# BBBL-CAN-GPS-RC-Interface.net
KiCad netlist of a schematic drawn in EAGLE
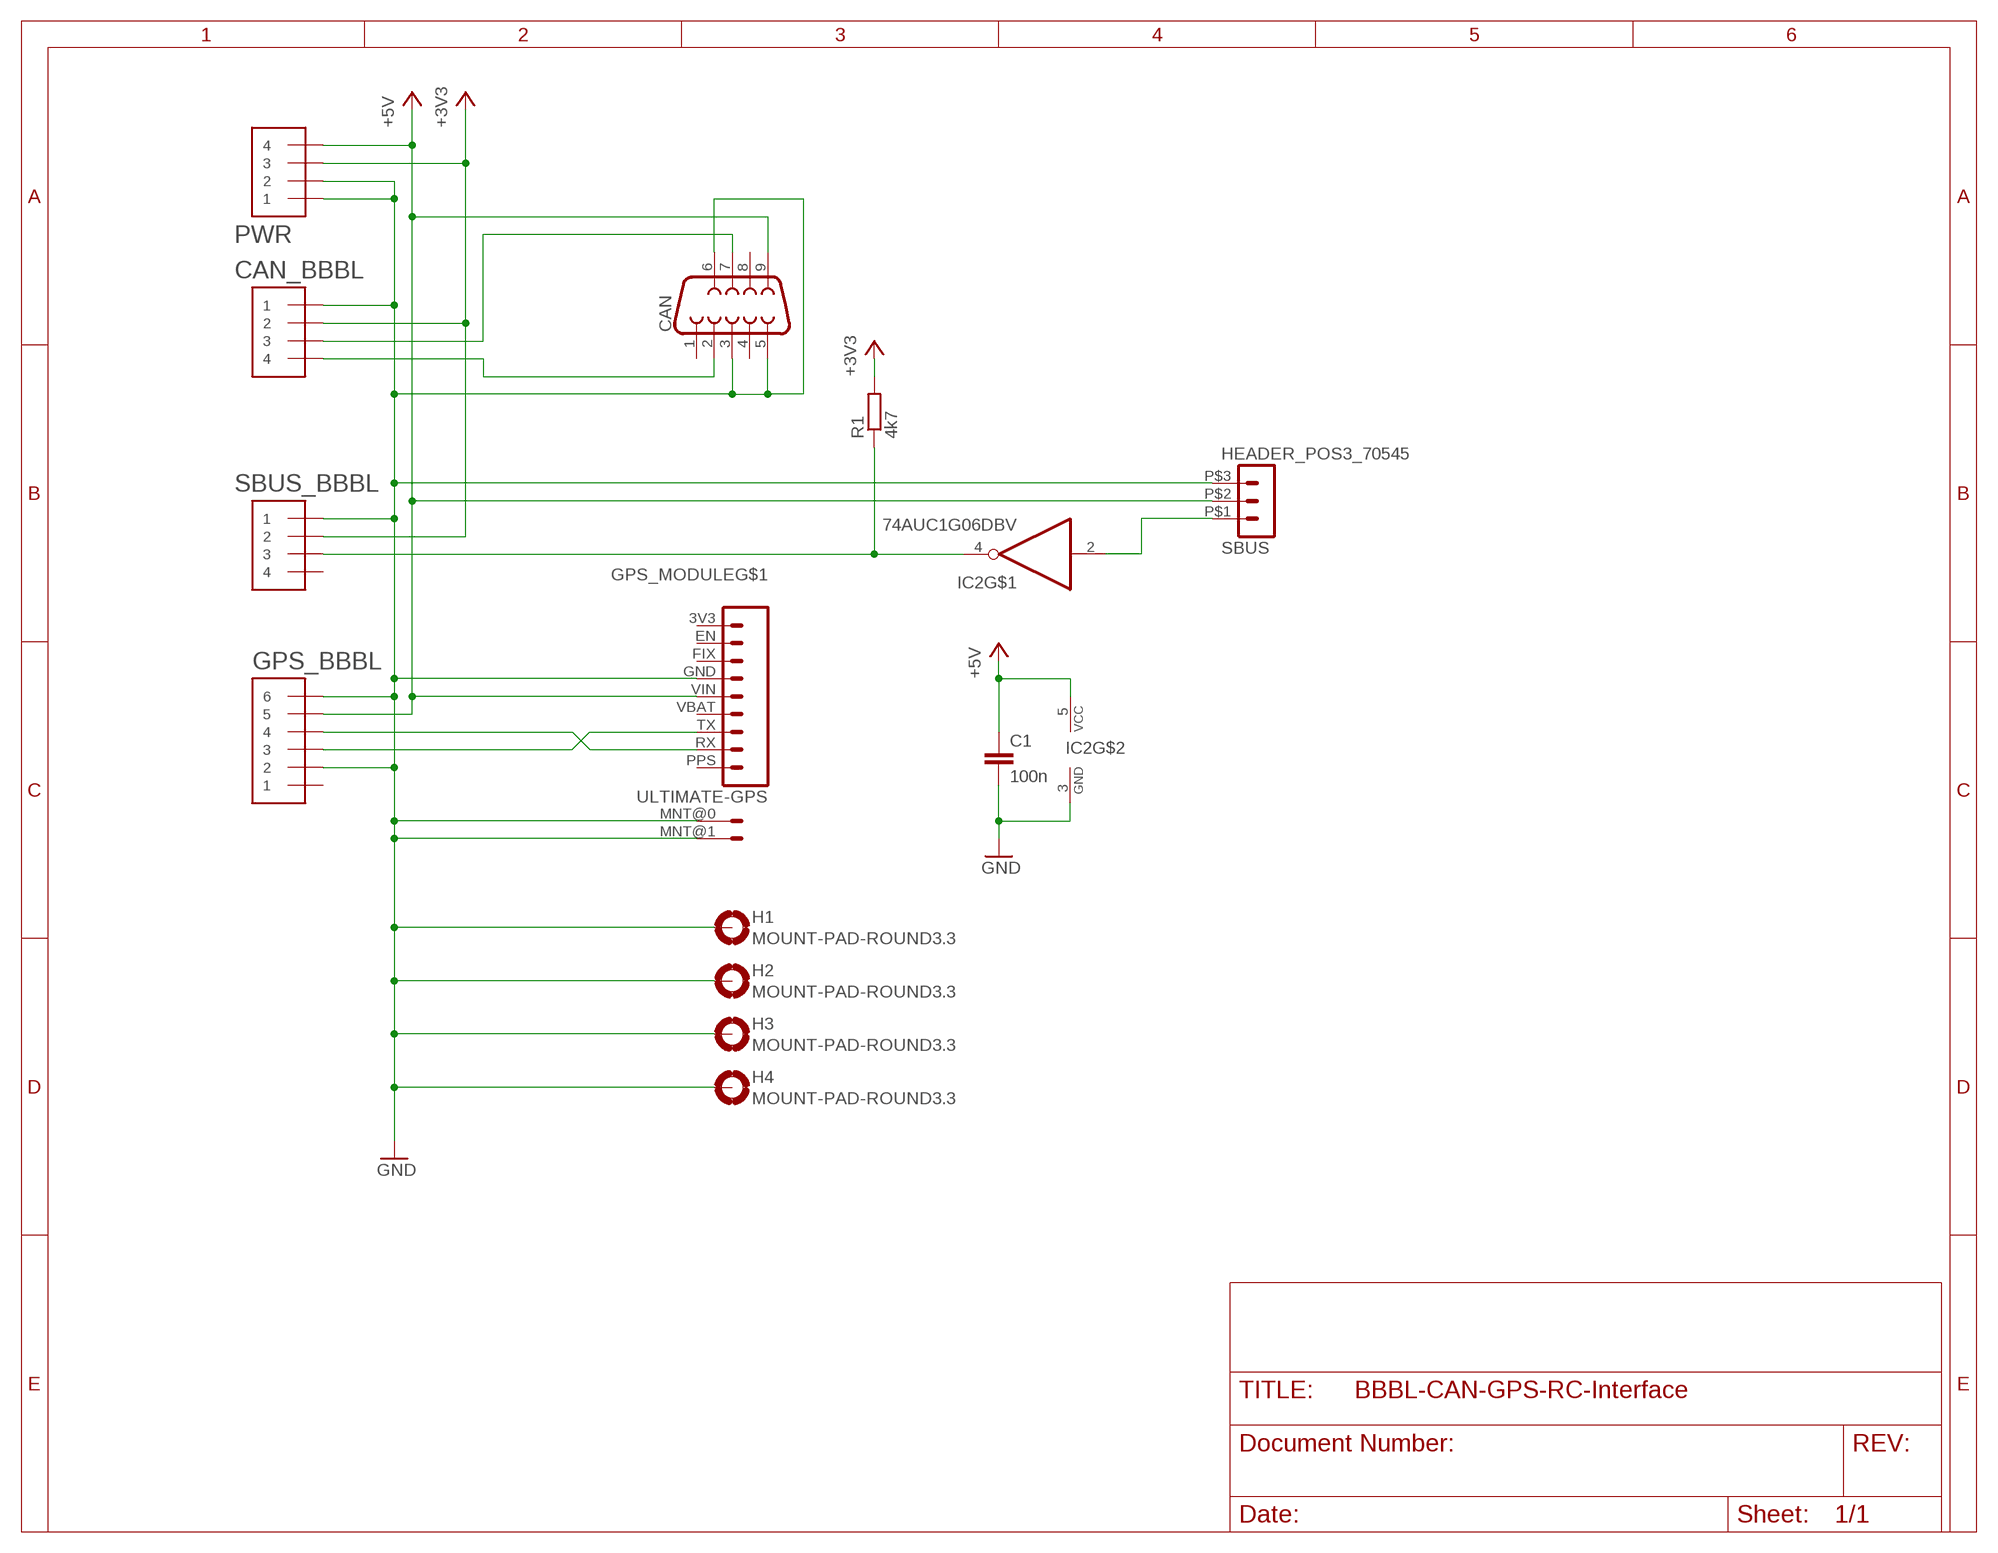
[diagram p0: schematic, sheet 1]

(export (version "E")
  (design (tool "Eeschema 10.0.6"))
  (components
    (comp (ref "C1")
      (value "100n")
      (footprint "eagle-import:C0603")
      (libsource (lib "eagle-import") (part "C-EUC0603"))
    )
    (comp (ref "CAN")
      (value "DB9MALE")
      (footprint "eagle-import:DB9_MALE")
      (libsource (lib "eagle-import") (part "DB9MALE"))
    )
    (comp (ref "CAN_BBBL")
      (value "STRAWSON_EAGLE_LIB_JST_SH_4")
      (footprint "eagle-import:STRAWSON_EAGLE_LIB_JST_SH_4_SMD")
      (libsource (lib "eagle-import") (part "STRAWSON_EAGLE_LIB_JST_SH_4"))
    )
    (comp (ref "GPS_BBBL")
      (value "STRAWSON_EAGLE_LIB_JST_SH_6")
      (footprint "eagle-import:STRAWSON_EAGLE_LIB_JST_SH_6")
      (libsource (lib "eagle-import") (part "STRAWSON_EAGLE_LIB_JST_SH_6"))
    )
    (comp (ref "GPS_MODULE")
      (value "ULTIMATE-GPS")
      (footprint "eagle-import:ULTIMATE-GPS")
      (libsource (lib "eagle-import") (part "ULTIMATE-GPS"))
    )
    (comp (ref "H1")
      (value "MOUNT-PAD-ROUND3.3")
      (footprint "eagle-import:3,3-PAD")
      (libsource (lib "eagle-import") (part "MOUNT-PAD-ROUND3.3"))
    )
    (comp (ref "H2")
      (value "MOUNT-PAD-ROUND3.3")
      (footprint "eagle-import:3,3-PAD")
      (libsource (lib "eagle-import") (part "MOUNT-PAD-ROUND3.3"))
    )
    (comp (ref "H3")
      (value "MOUNT-PAD-ROUND3.3")
      (footprint "eagle-import:3,3-PAD")
      (libsource (lib "eagle-import") (part "MOUNT-PAD-ROUND3.3"))
    )
    (comp (ref "H4")
      (value "MOUNT-PAD-ROUND3.3")
      (footprint "eagle-import:3,3-PAD")
      (libsource (lib "eagle-import") (part "MOUNT-PAD-ROUND3.3"))
    )
    (comp (ref "IC2")
      (value "74AUC1G06DBV")
      (footprint "eagle-import:SOT23-5")
      (libsource (lib "eagle-import") (part "741G06DBVAUC"))
    )
    (comp (ref "PWR")
      (value "STRAWSON_EAGLE_LIB_JST_SH_4")
      (footprint "eagle-import:STRAWSON_EAGLE_LIB_JST_SH_4_SMD")
      (libsource (lib "eagle-import") (part "STRAWSON_EAGLE_LIB_JST_SH_4"))
    )
    (comp (ref "R1")
      (value "4k7")
      (footprint "eagle-import:R0603")
      (libsource (lib "eagle-import") (part "R-EU_R0603"))
    )
    (comp (ref "SBUS")
      (value "HEADER_POS3_70545")
      (footprint "eagle-import:70545-POS3")
      (libsource (lib "eagle-import") (part "HEADER_POS3_?70545"))
    )
    (comp (ref "SBUS_BBBL")
      (value "STRAWSON_EAGLE_LIB_JST_SH_4")
      (footprint "eagle-import:STRAWSON_EAGLE_LIB_JST_SH_4_SMD")
      (libsource (lib "eagle-import") (part "STRAWSON_EAGLE_LIB_JST_SH_4"))
    )
  )
  (nets
    (net (code "1") (name "+3V3") (class "Default")
      (node (ref "CAN_BBBL") (pin "2") (pinfunction "2_2") (pintype "bidirectional"))
      (node (ref "PWR") (pin "3") (pinfunction "3_3") (pintype "bidirectional"))
      (node (ref "R1") (pin "2") (pinfunction "2_2") (pintype "passive"))
      (node (ref "SBUS_BBBL") (pin "2") (pinfunction "2_2") (pintype "bidirectional"))
    )
    (net (code "2") (name "+5V") (class "Default")
      (node (ref "C1") (pin "1") (pinfunction "1_1") (pintype "passive"))
      (node (ref "CAN") (pin "9") (pinfunction "9_9") (pintype "passive"))
      (node (ref "GPS_BBBL") (pin "5") (pinfunction "5_5") (pintype "bidirectional"))
      (node (ref "GPS_MODULE") (pin "VIN") (pinfunction "5_VIN") (pintype "passive"))
      (node (ref "IC2") (pin "5") (pinfunction "VCC_5") (pintype "power_in"))
      (node (ref "PWR") (pin "4") (pinfunction "4_4") (pintype "bidirectional"))
      (node (ref "SBUS") (pin "P$2") (pinfunction "2_P$2") (pintype "passive"))
    )
    (net (code "3") (name "GND") (class "Default")
      (node (ref "C1") (pin "2") (pinfunction "2_2") (pintype "passive"))
      (node (ref "CAN") (pin "3") (pinfunction "3_3") (pintype "passive"))
      (node (ref "CAN") (pin "5") (pinfunction "5_5") (pintype "passive"))
      (node (ref "CAN") (pin "6") (pinfunction "6_6") (pintype "passive"))
      (node (ref "CAN_BBBL") (pin "1") (pinfunction "1_1") (pintype "bidirectional"))
      (node (ref "GPS_BBBL") (pin "2") (pinfunction "2_2") (pintype "bidirectional"))
      (node (ref "GPS_BBBL") (pin "6") (pinfunction "6_6") (pintype "bidirectional"))
      (node (ref "GPS_MODULE") (pin "GND") (pinfunction "6_GND") (pintype "passive"))
      (node (ref "GPS_MODULE") (pin "MNT@0") (pinfunction "9_MNT@0") (pintype "passive"))
      (node (ref "GPS_MODULE") (pin "MNT@1") (pinfunction "9_MNT@1") (pintype "passive"))
      (node (ref "H1") (pin "B3,3") (pinfunction "MOUNT_B3,3") (pintype "passive"))
      (node (ref "H2") (pin "B3,3") (pinfunction "MOUNT_B3,3") (pintype "passive"))
      (node (ref "H3") (pin "B3,3") (pinfunction "MOUNT_B3,3") (pintype "passive"))
      (node (ref "H4") (pin "B3,3") (pinfunction "MOUNT_B3,3") (pintype "passive"))
      (node (ref "IC2") (pin "3") (pinfunction "GND_3") (pintype "power_in"))
      (node (ref "PWR") (pin "1") (pinfunction "1_1") (pintype "bidirectional"))
      (node (ref "PWR") (pin "2") (pinfunction "2_2") (pintype "bidirectional"))
      (node (ref "SBUS") (pin "P$3") (pinfunction "3_P$3") (pintype "passive"))
      (node (ref "SBUS_BBBL") (pin "1") (pinfunction "1_1") (pintype "bidirectional"))
    )
    (net (code "4") (name "Net-(CAN-Pad2)") (class "Default")
      (node (ref "CAN") (pin "2") (pinfunction "2_2") (pintype "passive"))
      (node (ref "CAN_BBBL") (pin "4") (pinfunction "4_4") (pintype "bidirectional"))
    )
    (net (code "5") (name "Net-(CAN-Pad7)") (class "Default")
      (node (ref "CAN") (pin "7") (pinfunction "7_7") (pintype "passive"))
      (node (ref "CAN_BBBL") (pin "3") (pinfunction "3_3") (pintype "bidirectional"))
    )
    (net (code "6") (name "Net-(GPS_MODULEA-2)") (class "Default")
      (node (ref "GPS_BBBL") (pin "4") (pinfunction "4_4") (pintype "bidirectional"))
      (node (ref "GPS_MODULE") (pin "RX") (pinfunction "2_RX") (pintype "passive"))
    )
    (net (code "7") (name "Net-(GPS_MODULEA-3)") (class "Default")
      (node (ref "GPS_BBBL") (pin "3") (pinfunction "3_3") (pintype "bidirectional"))
      (node (ref "GPS_MODULE") (pin "TX") (pinfunction "3_TX") (pintype "passive"))
    )
    (net (code "8") (name "Net-(IC2A-I)") (class "Default")
      (node (ref "IC2") (pin "2") (pinfunction "I_2") (pintype "input"))
      (node (ref "SBUS") (pin "P$1") (pinfunction "1_P$1") (pintype "passive"))
    )
    (net (code "9") (name "Net-(IC2A-O)") (class "Default")
      (node (ref "IC2") (pin "4") (pinfunction "O_4") (pintype "open_collector"))
      (node (ref "R1") (pin "1") (pinfunction "1_1") (pintype "passive"))
      (node (ref "SBUS_BBBL") (pin "3") (pinfunction "3_3") (pintype "bidirectional"))
    )
    (net (code "10") (name "unconnected-(CAN-Pad1)") (class "Default")
      (node (ref "CAN") (pin "1") (pinfunction "1_1") (pintype "passive"))
    )
    (net (code "11") (name "unconnected-(CAN-Pad4)") (class "Default")
      (node (ref "CAN") (pin "4") (pinfunction "4_4") (pintype "passive"))
    )
    (net (code "12") (name "unconnected-(CAN-Pad8)") (class "Default")
      (node (ref "CAN") (pin "8") (pinfunction "8_8") (pintype "passive"))
    )
    (net (code "13") (name "unconnected-(GPS_BBBL-Pad1)") (class "Default")
      (node (ref "GPS_BBBL") (pin "1") (pinfunction "1_1") (pintype "bidirectional"))
    )
    (net (code "14") (name "unconnected-(GPS_MODULEA-1-PadPPS)") (class "Default")
      (node (ref "GPS_MODULE") (pin "PPS") (pinfunction "1_PPS") (pintype "passive"))
    )
    (net (code "15") (name "unconnected-(GPS_MODULEA-4-PadVBAT)") (class "Default")
      (node (ref "GPS_MODULE") (pin "VBAT") (pinfunction "4_VBAT") (pintype "passive"))
    )
    (net (code "16") (name "unconnected-(GPS_MODULEA-7-PadFIX)") (class "Default")
      (node (ref "GPS_MODULE") (pin "FIX") (pinfunction "7_FIX") (pintype "passive"))
    )
    (net (code "17") (name "unconnected-(GPS_MODULEA-8-PadEN)") (class "Default")
      (node (ref "GPS_MODULE") (pin "EN") (pinfunction "8_EN") (pintype "passive"))
    )
    (net (code "18") (name "unconnected-(GPS_MODULEA-9-Pad3V3)") (class "Default")
      (node (ref "GPS_MODULE") (pin "3V3") (pinfunction "9_3V3") (pintype "passive"))
    )
    (net (code "19") (name "unconnected-(SBUS_BBBL-Pad4)") (class "Default")
      (node (ref "SBUS_BBBL") (pin "4") (pinfunction "4_4") (pintype "bidirectional"))
    )
  )
)
